# Flash_Memory.net
KiCad netlist of a schematic drawn in Altium Designer
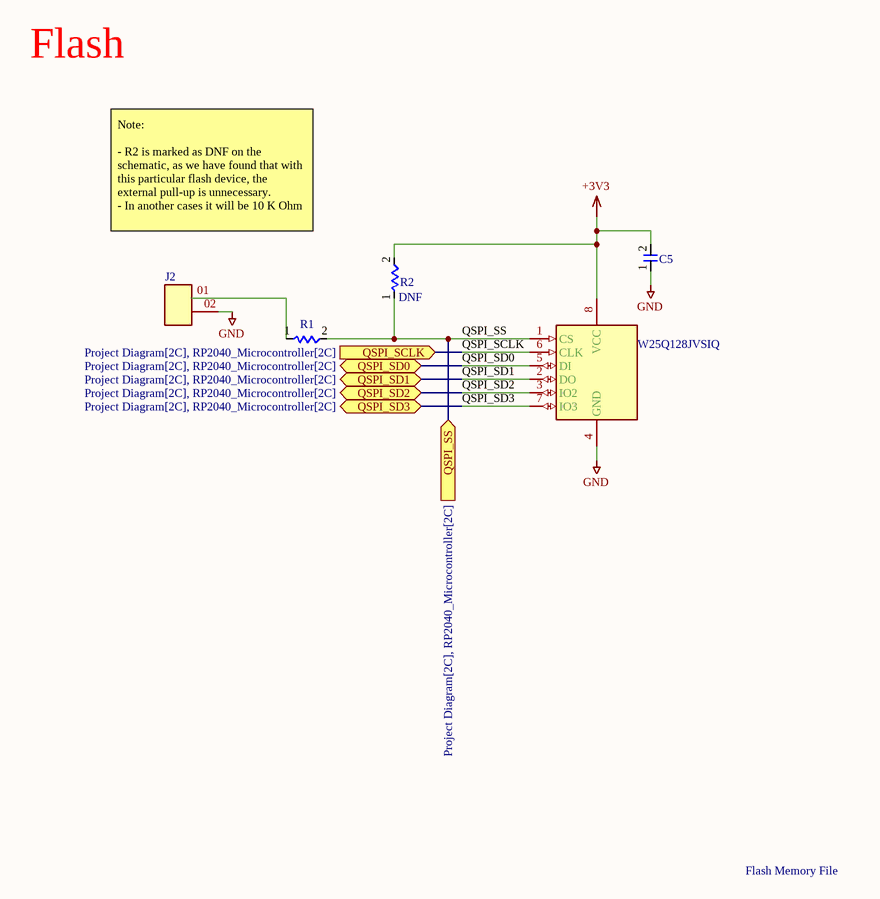
[diagram p0: Flash Memory.SchDoc]

(export (version "E")
  (design (tool "Eeschema 10.0.6"))
  (components
    (comp (ref "C5")
      (value "10UF Capacitor")
      (footprint "CC0603KRX5R8BB104")
      (description "100 nF ±10% 25V Ceramic Capacitor X5R 0603 (1608 Metric)")
      (fields (field (name "PART NUMBER") "CL21A106KOQNNNE"))
      (libsource (lib "RP2040_Integrated_Library") (part "CC0603KRX5R8BB104"))
    )
    (comp (ref "J2")
      (value "Header 1x2")
      (footprint "Header 1x2")
      (libsource (lib "RP2040_Integrated_Library") (part "Header 1x2"))
    )
    (comp (ref "R1")
      (value "1 KOhm")
      (footprint "RC1206FR-078K06L")
      (description "8.06 kOhms ±1% 0.25W, 1/4W Chip Resistor 1206 (3216 Metric) Moisture Resistant Thick Film")
      (fields (field (name "PART NUMBER") "RC1206FR-078K06L"))
      (libsource (lib "RP2040_Integrated_Library") (part "RC1206FR-078K06L"))
    )
    (comp (ref "R2")
      (value "1 KOhm")
      (footprint "RC1206FR-078K06L")
      (description "8.06 kOhms ±1% 0.25W, 1/4W Chip Resistor 1206 (3216 Metric) Moisture Resistant Thick Film")
      (fields (field (name "PART NUMBER") "RC1206FR-078K06L"))
      (libsource (lib "RP2040_Integrated_Library") (part "RC1206FR-078K06L"))
    )
    (comp (ref "U2")
      (value "W25Q128JVSIQ")
      (footprint "W25Q128JVSIQ-ND")
      (description "FLASH - NOR Memory IC 128Mbit SPI - Quad I/O, QPI 133 MHz 8-SOIC")
      (libsource (lib "RP2040_Integrated_Library") (part "W25Q128JVSIQ"))
    )
  )
  (nets
    (net (code "1") (name "+3V3") (class "Default")
      (node (ref "C5") (pin "2") (pinfunction "Pin_2_2") (pintype "passive"))
      (node (ref "R2") (pin "2") (pinfunction "pin_2_2") (pintype "passive"))
      (node (ref "U2") (pin "8") (pinfunction "VCC_8") (pintype "power_in"))
    )
    (net (code "2") (name "/QSPI_SCLK") (class "Default")
      (node (ref "U2") (pin "6") (pinfunction "CLK_6") (pintype "input"))
    )
    (net (code "3") (name "/QSPI_SD0") (class "Default")
      (node (ref "U2") (pin "5") (pinfunction "DI_5") (pintype "bidirectional"))
    )
    (net (code "4") (name "/QSPI_SD1") (class "Default")
      (node (ref "U2") (pin "2") (pinfunction "DO_2") (pintype "bidirectional"))
    )
    (net (code "5") (name "/QSPI_SD2") (class "Default")
      (node (ref "U2") (pin "3") (pinfunction "IO2_3") (pintype "bidirectional"))
    )
    (net (code "6") (name "/QSPI_SD3") (class "Default")
      (node (ref "U2") (pin "7") (pinfunction "IO3_7") (pintype "bidirectional"))
    )
    (net (code "7") (name "/QSPI_SS") (class "Default")
      (node (ref "R1") (pin "2") (pinfunction "pin_2_2") (pintype "passive"))
      (node (ref "R2") (pin "1") (pinfunction "Pin_1_1") (pintype "passive"))
      (node (ref "U2") (pin "1") (pinfunction "CS_1") (pintype "input"))
    )
    (net (code "8") (name "GND") (class "Default")
      (node (ref "C5") (pin "1") (pinfunction "Pin_1_1") (pintype "passive"))
      (node (ref "J2") (pin "02") (pinfunction "02_02") (pintype "passive"))
      (node (ref "U2") (pin "4") (pinfunction "GND_4") (pintype "power_in"))
    )
    (net (code "9") (name "Net-(R1-Pin_1)") (class "Default")
      (node (ref "J2") (pin "01") (pinfunction "01_01") (pintype "passive"))
      (node (ref "R1") (pin "1") (pinfunction "Pin_1_1") (pintype "passive"))
    )
  )
)
